# DriveUnit_B-series_ver1_0.net
KiCad netlist of a schematic drawn in EAGLE
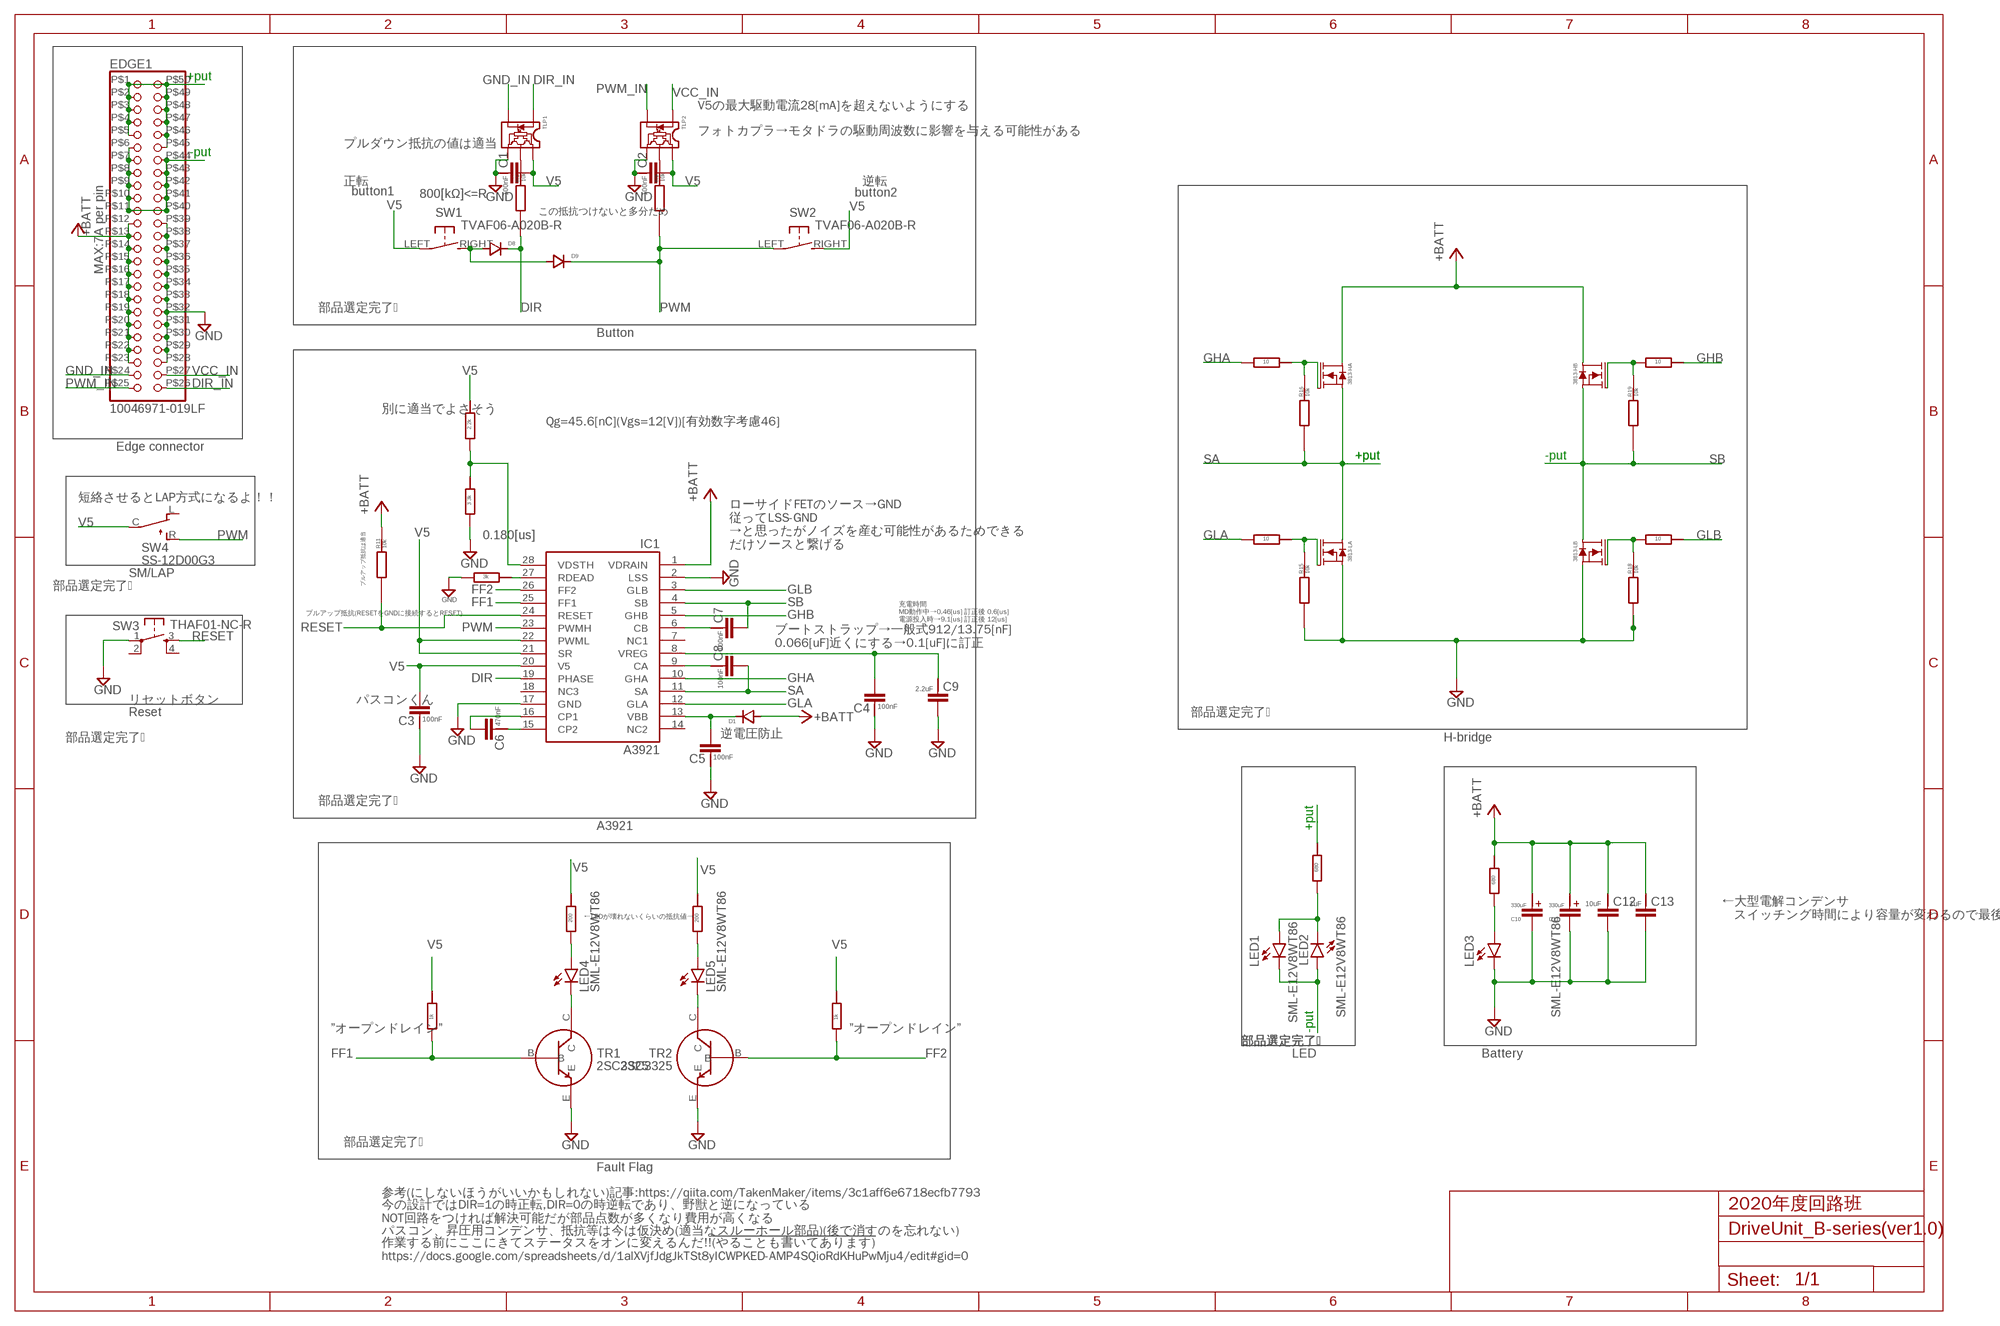
[diagram p0: schematic, sheet 1]

(export (version "E")
  (design (tool "Eeschema 10.0.6"))
  (components
    (comp (ref "3813-HA")
      (value "IRLB3813NOHOLE")
      (footprint "eagle-import:TO-220AB-NOHOLE")
      (libsource (lib "eagle-import") (part "IRLB3813NOHOLE"))
    )
    (comp (ref "3813-HB")
      (value "IRLB3813NOHOLE")
      (footprint "eagle-import:TO-220AB-NOHOLE")
      (libsource (lib "eagle-import") (part "IRLB3813NOHOLE"))
    )
    (comp (ref "3813-LA")
      (value "IRLB3813NOHOLE")
      (footprint "eagle-import:TO-220AB-NOHOLE")
      (libsource (lib "eagle-import") (part "IRLB3813NOHOLE"))
    )
    (comp (ref "3813-LB")
      (value "IRLB3813NOHOLE")
      (footprint "eagle-import:TO-220AB-NOHOLE")
      (libsource (lib "eagle-import") (part "IRLB3813NOHOLE"))
    )
    (comp (ref "C1")
      (value "GCM188L81H104KA57")
      (footprint "eagle-import:GCM188L81H104KA57")
      (libsource (lib "eagle-import") (part "GCM188L81H104KA57"))
    )
    (comp (ref "C2")
      (value "GCM188L81H104KA57")
      (footprint "eagle-import:GCM188L81H104KA57")
      (libsource (lib "eagle-import") (part "GCM188L81H104KA57"))
    )
    (comp (ref "C3")
      (value "GCM188L81H104KA57")
      (footprint "eagle-import:GCM188L81H104KA57")
      (libsource (lib "eagle-import") (part "GCM188L81H104KA57"))
    )
    (comp (ref "C4")
      (value "GCM188L81H104KA57")
      (footprint "eagle-import:GCM188L81H104KA57")
      (libsource (lib "eagle-import") (part "GCM188L81H104KA57"))
    )
    (comp (ref "C5")
      (value "GCM188L81H104KA57")
      (footprint "eagle-import:GCM188L81H104KA57")
      (libsource (lib "eagle-import") (part "GCM188L81H104KA57"))
    )
    (comp (ref "C6")
      (value "GCM21BR71H474KA55")
      (footprint "eagle-import:GCM21BR71H474KA55")
      (libsource (lib "eagle-import") (part "GCM21BR71H474KA55"))
    )
    (comp (ref "C7")
      (value "GCM188L81H104KA57")
      (footprint "eagle-import:GCM188L81H104KA57")
      (libsource (lib "eagle-import") (part "GCM188L81H104KA57"))
    )
    (comp (ref "C8")
      (value "GCM188L81H104KA57")
      (footprint "eagle-import:GCM188L81H104KA57")
      (libsource (lib "eagle-import") (part "GCM188L81H104KA57"))
    )
    (comp (ref "C9")
      (value "GRT31CC81H225KE01L")
      (footprint "eagle-import:GRT31CC81H225KE01L")
      (libsource (lib "eagle-import") (part "GRT31CC81H225KE01L"))
    )
    (comp (ref "C10")
      (value "35PZJ330M10X9")
      (footprint "eagle-import:35PZJ330M10X9")
      (libsource (lib "eagle-import") (part "35PZJ330M10X9"))
    )
    (comp (ref "C11")
      (value "35PZJ330M10X9")
      (footprint "eagle-import:35PZJ330M10X9")
      (libsource (lib "eagle-import") (part "35PZJ330M10X9"))
    )
    (comp (ref "C12")
      (value "GRM32ER7YA106KA12")
      (footprint "eagle-import:GRM32ER7YA106KA12")
      (libsource (lib "eagle-import") (part "GRM32ER7YA106KA12"))
    )
    (comp (ref "C13")
      (value "GRM21BC72A105KE01")
      (footprint "eagle-import:GRM21BC72A105KE01")
      (libsource (lib "eagle-import") (part "GRM21BC72A105KE01"))
    )
    (comp (ref "D1")
      (value "GS1010FL")
      (footprint "eagle-import:GS1010FL")
      (libsource (lib "eagle-import") (part "GS1010FL"))
    )
    (comp (ref "D8")
      (value "GS1010FL")
      (footprint "eagle-import:GS1010FL")
      (libsource (lib "eagle-import") (part "GS1010FL"))
    )
    (comp (ref "D9")
      (value "GS1010FL")
      (footprint "eagle-import:GS1010FL")
      (libsource (lib "eagle-import") (part "GS1010FL"))
    )
    (comp (ref "EDGE1")
      (value "10046971-019LF")
      (footprint "eagle-import:10046971-019LF")
      (libsource (lib "eagle-import") (part "10046971-019LF"))
    )
    (comp (ref "IC1")
      (value "A3921")
      (footprint "eagle-import:A3921")
      (libsource (lib "eagle-import") (part "A3921"))
    )
    (comp (ref "LED1")
      (value "SML-E12V8WT86")
      (footprint "eagle-import:SML-E12V8WT86")
      (libsource (lib "eagle-import") (part "SML-E12V8WT86"))
    )
    (comp (ref "LED2")
      (value "SML-E12V8WT86")
      (footprint "eagle-import:SML-E12V8WT86")
      (libsource (lib "eagle-import") (part "SML-E12V8WT86"))
    )
    (comp (ref "LED3")
      (value "SML-E12V8WT86")
      (footprint "eagle-import:SML-E12V8WT86")
      (libsource (lib "eagle-import") (part "SML-E12V8WT86"))
    )
    (comp (ref "LED4")
      (value "SML-E12V8WT86")
      (footprint "eagle-import:SML-E12V8WT86")
      (libsource (lib "eagle-import") (part "SML-E12V8WT86"))
    )
    (comp (ref "LED5")
      (value "SML-E12V8WT86")
      (footprint "eagle-import:SML-E12V8WT86")
      (libsource (lib "eagle-import") (part "SML-E12V8WT86"))
    )
    (comp (ref "R1")
      (value "RG2012")
      (footprint "eagle-import:RG2012")
      (libsource (lib "eagle-import") (part "RG2012"))
    )
    (comp (ref "R2")
      (value "RG2012N-332-W-T1")
      (footprint "eagle-import:RG2012")
      (libsource (lib "eagle-import") (part "RG2012N-332-W-T1"))
    )
    (comp (ref "R3")
      (value "RG2012P-681-B-T5")
      (footprint "eagle-import:RG2012")
      (libsource (lib "eagle-import") (part "RG2012P-681-B-T5"))
    )
    (comp (ref "R5")
      (value "RG2012-N-102-B-T5")
      (footprint "eagle-import:RG2012")
      (libsource (lib "eagle-import") (part "RG2012-N-102-B-T5"))
    )
    (comp (ref "R6")
      (value "RG2012-N-102-B-T5")
      (footprint "eagle-import:RG2012")
      (libsource (lib "eagle-import") (part "RG2012-N-102-B-T5"))
    )
    (comp (ref "R7")
      (value "RG2012N-201-W-T1")
      (footprint "eagle-import:RG2012")
      (libsource (lib "eagle-import") (part "RG2012N-201-W-T1"))
    )
    (comp (ref "R8")
      (value "RG2012N-201-W-T1")
      (footprint "eagle-import:RG2012")
      (libsource (lib "eagle-import") (part "RG2012N-201-W-T1"))
    )
    (comp (ref "R9")
      (value "RG2012")
      (footprint "eagle-import:RG2012")
      (libsource (lib "eagle-import") (part "RG2012"))
    )
    (comp (ref "R10")
      (value "RG2012Q-100-D-T5")
      (footprint "eagle-import:RG2012")
      (libsource (lib "eagle-import") (part "RG2012Q-100-D-T5"))
    )
    (comp (ref "R11")
      (value "RG2012")
      (footprint "eagle-import:RG2012")
      (libsource (lib "eagle-import") (part "RG2012"))
    )
    (comp (ref "R12")
      (value "RG2012Q-100-D-T5")
      (footprint "eagle-import:RG2012")
      (libsource (lib "eagle-import") (part "RG2012Q-100-D-T5"))
    )
    (comp (ref "R13")
      (value "RG2012P-302-B-T5")
      (footprint "eagle-import:RG2012")
      (libsource (lib "eagle-import") (part "RG2012P-302-B-T5"))
    )
    (comp (ref "R14")
      (value "RG2012N-222-W-T1")
      (footprint "eagle-import:RG2012")
      (libsource (lib "eagle-import") (part "RG2012N-222-W-T1"))
    )
    (comp (ref "R15")
      (value "RG2012")
      (footprint "eagle-import:RG2012")
      (libsource (lib "eagle-import") (part "RG2012"))
    )
    (comp (ref "R16")
      (value "RG2012")
      (footprint "eagle-import:RG2012")
      (libsource (lib "eagle-import") (part "RG2012"))
    )
    (comp (ref "R18")
      (value "RG2012")
      (footprint "eagle-import:RG2012")
      (libsource (lib "eagle-import") (part "RG2012"))
    )
    (comp (ref "R19")
      (value "RG2012")
      (footprint "eagle-import:RG2012")
      (libsource (lib "eagle-import") (part "RG2012"))
    )
    (comp (ref "R20")
      (value "RG2012Q-100-D-T5")
      (footprint "eagle-import:RG2012")
      (libsource (lib "eagle-import") (part "RG2012Q-100-D-T5"))
    )
    (comp (ref "R21")
      (value "RG2012Q-100-D-T5")
      (footprint "eagle-import:RG2012")
      (libsource (lib "eagle-import") (part "RG2012Q-100-D-T5"))
    )
    (comp (ref "R22")
      (value "RG2012P-681-B-T5")
      (footprint "eagle-import:RG2012")
      (libsource (lib "eagle-import") (part "RG2012P-681-B-T5"))
    )
    (comp (ref "SW1")
      (value "TVAF06-A020B-R")
      (footprint "eagle-import:TVAF06-A020B-R")
      (libsource (lib "eagle-import") (part "TVAF06-A020B-R"))
    )
    (comp (ref "SW2")
      (value "TVAF06-A020B-R")
      (footprint "eagle-import:TVAF06-A020B-R")
      (libsource (lib "eagle-import") (part "TVAF06-A020B-R"))
    )
    (comp (ref "SW3")
      (value "THAF01-NC-R")
      (footprint "eagle-import:THAF01-NC-R")
      (libsource (lib "eagle-import") (part "THAF01-NC-R"))
    )
    (comp (ref "SW4")
      (value "SS-12D00G3")
      (footprint "eagle-import:SS-12D00G3")
      (libsource (lib "eagle-import") (part "SS-12D00G3"))
    )
    (comp (ref "TLP1")
      (value "TLP2366")
      (footprint "eagle-import:TLP2366")
      (libsource (lib "eagle-import") (part "TLP2366"))
    )
    (comp (ref "TLP2")
      (value "TLP2366")
      (footprint "eagle-import:TLP2366")
      (libsource (lib "eagle-import") (part "TLP2366"))
    )
    (comp (ref "TR1")
      (value "2SC3325")
      (footprint "eagle-import:2SC3325")
      (libsource (lib "eagle-import") (part "2SC3325"))
    )
    (comp (ref "TR2")
      (value "2SC3325")
      (footprint "eagle-import:2SC3325")
      (libsource (lib "eagle-import") (part "2SC3325"))
    )
  )
  (nets
    (net (code "1") (name "+BATT") (class "Default")
      (node (ref "3813-HA") (pin "DRAIN") (pinfunction "D_DRAIN") (pintype "passive"))
      (node (ref "3813-HB") (pin "DRAIN") (pinfunction "D_DRAIN") (pintype "passive"))
      (node (ref "C10") (pin "A") (pinfunction "ANODE_A") (pintype "bidirectional"))
      (node (ref "C11") (pin "A") (pinfunction "ANODE_A") (pintype "bidirectional"))
      (node (ref "C12") (pin "P$1") (pinfunction "P$1_P$1") (pintype "bidirectional"))
      (node (ref "C13") (pin "P$1") (pinfunction "P$1_P$1") (pintype "bidirectional"))
      (node (ref "D1") (pin "A") (pinfunction "A_A") (pintype "passive"))
      (node (ref "EDGE1") (pin "P$12") (pinfunction "P12_P$12") (pintype "passive"))
      (node (ref "EDGE1") (pin "P$13") (pinfunction "P13_P$13") (pintype "passive"))
      (node (ref "EDGE1") (pin "P$14") (pinfunction "P14_P$14") (pintype "passive"))
      (node (ref "EDGE1") (pin "P$15") (pinfunction "P15_P$15") (pintype "passive"))
      (node (ref "EDGE1") (pin "P$16") (pinfunction "P16_P$16") (pintype "passive"))
      (node (ref "EDGE1") (pin "P$17") (pinfunction "P17_P$17") (pintype "passive"))
      (node (ref "EDGE1") (pin "P$18") (pinfunction "P18_P$18") (pintype "passive"))
      (node (ref "EDGE1") (pin "P$19") (pinfunction "P19_P$19") (pintype "passive"))
      (node (ref "EDGE1") (pin "P$20") (pinfunction "P20_P$20") (pintype "passive"))
      (node (ref "EDGE1") (pin "P$21") (pinfunction "P21_P$21") (pintype "passive"))
      (node (ref "EDGE1") (pin "P$22") (pinfunction "P22_P$22") (pintype "passive"))
      (node (ref "EDGE1") (pin "P$23") (pinfunction "P23_P$23") (pintype "passive"))
      (node (ref "IC1") (pin "1") (pinfunction "VDRAIN_1") (pintype "bidirectional"))
      (node (ref "R11") (pin "RIGHT") (pinfunction "RIGHT_RIGHT") (pintype "bidirectional"))
      (node (ref "R22") (pin "LEFT") (pinfunction "P$1_LEFT") (pintype "bidirectional"))
    )
    (net (code "2") (name "/DIR") (class "Default")
      (node (ref "D8") (pin "C") (pinfunction "C_C") (pintype "passive"))
      (node (ref "IC1") (pin "19") (pinfunction "PHASE_19") (pintype "bidirectional"))
      (node (ref "R1") (pin "LEFT") (pinfunction "LEFT_LEFT") (pintype "bidirectional"))
    )
    (net (code "3") (name "/DIR_IN") (class "Default")
      (node (ref "EDGE1") (pin "P$26") (pinfunction "P26_P$26") (pintype "passive"))
      (node (ref "TLP1") (pin "1") (pinfunction "ANODE_1") (pintype "passive"))
    )
    (net (code "4") (name "/FF1") (class "Default")
      (node (ref "IC1") (pin "25") (pinfunction "FF1_25") (pintype "bidirectional"))
      (node (ref "R5") (pin "RIGHT") (pinfunction "P$2_RIGHT") (pintype "bidirectional"))
      (node (ref "TR1") (pin "B") (pinfunction "B_B") (pintype "bidirectional"))
    )
    (net (code "5") (name "/FF2") (class "Default")
      (node (ref "IC1") (pin "26") (pinfunction "FF2_26") (pintype "bidirectional"))
      (node (ref "R6") (pin "RIGHT") (pinfunction "P$2_RIGHT") (pintype "bidirectional"))
      (node (ref "TR2") (pin "B") (pinfunction "B_B") (pintype "bidirectional"))
    )
    (net (code "6") (name "/GHA") (class "Default")
      (node (ref "IC1") (pin "10") (pinfunction "GHA_10") (pintype "bidirectional"))
      (node (ref "R21") (pin "RIGHT") (pinfunction "P$2_RIGHT") (pintype "bidirectional"))
    )
    (net (code "7") (name "/GHB") (class "Default")
      (node (ref "IC1") (pin "5") (pinfunction "GHB_5") (pintype "bidirectional"))
      (node (ref "R12") (pin "LEFT") (pinfunction "P$1_LEFT") (pintype "bidirectional"))
    )
    (net (code "8") (name "/GLA") (class "Default")
      (node (ref "IC1") (pin "12") (pinfunction "GLA_12") (pintype "bidirectional"))
      (node (ref "R20") (pin "RIGHT") (pinfunction "P$2_RIGHT") (pintype "bidirectional"))
    )
    (net (code "9") (name "/GLB") (class "Default")
      (node (ref "IC1") (pin "3") (pinfunction "GLB_3") (pintype "bidirectional"))
      (node (ref "R10") (pin "LEFT") (pinfunction "P$1_LEFT") (pintype "bidirectional"))
    )
    (net (code "10") (name "/GND_IN") (class "Default")
      (node (ref "EDGE1") (pin "P$24") (pinfunction "P24_P$24") (pintype "passive"))
      (node (ref "TLP1") (pin "3") (pinfunction "CATHODE_3") (pintype "passive"))
    )
    (net (code "11") (name "/PWM") (class "Default")
      (node (ref "D9") (pin "C") (pinfunction "C_C") (pintype "passive"))
      (node (ref "IC1") (pin "23") (pinfunction "PWMH_23") (pintype "bidirectional"))
      (node (ref "R9") (pin "LEFT") (pinfunction "LEFT_LEFT") (pintype "bidirectional"))
      (node (ref "SW2") (pin "LEFT") (pinfunction "P_LEFT") (pintype "passive"))
      (node (ref "SW4") (pin "R") (pinfunction "R_R") (pintype "passive"))
    )
    (net (code "12") (name "/PWM_IN") (class "Default")
      (node (ref "EDGE1") (pin "P$25") (pinfunction "P25_P$25") (pintype "passive"))
      (node (ref "TLP2") (pin "3") (pinfunction "CATHODE_3") (pintype "passive"))
    )
    (net (code "13") (name "/RESET") (class "Default")
      (node (ref "IC1") (pin "24") (pinfunction "RESET_24") (pintype "bidirectional"))
      (node (ref "R11") (pin "LEFT") (pinfunction "LEFT_LEFT") (pintype "bidirectional"))
      (node (ref "SW3") (pin "3") (pinfunction "3_3") (pintype "passive"))
    )
    (net (code "14") (name "/SA") (class "Default")
      (node (ref "3813-HA") (pin "SOURCE") (pinfunction "S_SOURCE") (pintype "passive"))
      (node (ref "3813-LA") (pin "DRAIN") (pinfunction "D_DRAIN") (pintype "passive"))
      (node (ref "C8") (pin "P$2") (pinfunction "P$2_P$2") (pintype "bidirectional"))
      (node (ref "EDGE1") (pin "P$1") (pinfunction "P1_P$1") (pintype "passive"))
      (node (ref "EDGE1") (pin "P$2") (pinfunction "P2_P$2") (pintype "passive"))
      (node (ref "EDGE1") (pin "P$3") (pinfunction "P3_P$3") (pintype "passive"))
      (node (ref "EDGE1") (pin "P$4") (pinfunction "P4_P$4") (pintype "passive"))
      (node (ref "EDGE1") (pin "P$45") (pinfunction "P45_P$45") (pintype "passive"))
      (node (ref "EDGE1") (pin "P$46") (pinfunction "P46_P$46") (pintype "passive"))
      (node (ref "EDGE1") (pin "P$47") (pinfunction "P47_P$47") (pintype "passive"))
      (node (ref "EDGE1") (pin "P$48") (pinfunction "P48_P$48") (pintype "passive"))
      (node (ref "EDGE1") (pin "P$49") (pinfunction "P49_P$49") (pintype "passive"))
      (node (ref "EDGE1") (pin "P$5") (pinfunction "P5_P$5") (pintype "passive"))
      (node (ref "EDGE1") (pin "P$50") (pinfunction "P50_P$50") (pintype "passive"))
      (node (ref "IC1") (pin "11") (pinfunction "SA_11") (pintype "bidirectional"))
      (node (ref "R16") (pin "LEFT") (pinfunction "LEFT_LEFT") (pintype "bidirectional"))
      (node (ref "R3") (pin "LEFT") (pinfunction "P$1_LEFT") (pintype "bidirectional"))
    )
    (net (code "15") (name "/SB") (class "Default")
      (node (ref "3813-HB") (pin "SOURCE") (pinfunction "S_SOURCE") (pintype "passive"))
      (node (ref "3813-LB") (pin "DRAIN") (pinfunction "D_DRAIN") (pintype "passive"))
      (node (ref "C7") (pin "P$2") (pinfunction "P$2_P$2") (pintype "bidirectional"))
      (node (ref "EDGE1") (pin "P$10") (pinfunction "P10_P$10") (pintype "passive"))
      (node (ref "EDGE1") (pin "P$11") (pinfunction "P11_P$11") (pintype "passive"))
      (node (ref "EDGE1") (pin "P$40") (pinfunction "P40_P$40") (pintype "passive"))
      (node (ref "EDGE1") (pin "P$41") (pinfunction "P41_P$41") (pintype "passive"))
      (node (ref "EDGE1") (pin "P$42") (pinfunction "P42_P$42") (pintype "passive"))
      (node (ref "EDGE1") (pin "P$43") (pinfunction "P43_P$43") (pintype "passive"))
      (node (ref "EDGE1") (pin "P$44") (pinfunction "P44_P$44") (pintype "passive"))
      (node (ref "EDGE1") (pin "P$6") (pinfunction "P6_P$6") (pintype "passive"))
      (node (ref "EDGE1") (pin "P$7") (pinfunction "P7_P$7") (pintype "passive"))
      (node (ref "EDGE1") (pin "P$8") (pinfunction "P8_P$8") (pintype "passive"))
      (node (ref "EDGE1") (pin "P$9") (pinfunction "P9_P$9") (pintype "passive"))
      (node (ref "IC1") (pin "4") (pinfunction "SB_4") (pintype "bidirectional"))
      (node (ref "LED1") (pin "K") (pinfunction "C_K") (pintype "passive"))
      (node (ref "LED2") (pin "A") (pinfunction "A_A") (pintype "passive"))
      (node (ref "R19") (pin "LEFT") (pinfunction "LEFT_LEFT") (pintype "bidirectional"))
    )
    (net (code "16") (name "/V5") (class "Default")
      (node (ref "C1") (pin "P$2") (pinfunction "P$2_P$2") (pintype "bidirectional"))
      (node (ref "C2") (pin "P$2") (pinfunction "P$2_P$2") (pintype "bidirectional"))
      (node (ref "C3") (pin "P$2") (pinfunction "P$2_P$2") (pintype "bidirectional"))
      (node (ref "IC1") (pin "20") (pinfunction "V5_20") (pintype "bidirectional"))
      (node (ref "IC1") (pin "21") (pinfunction "SR_21") (pintype "bidirectional"))
      (node (ref "IC1") (pin "22") (pinfunction "PWML_22") (pintype "bidirectional"))
      (node (ref "R14") (pin "LEFT") (pinfunction "P$1_LEFT") (pintype "bidirectional"))
      (node (ref "R5") (pin "LEFT") (pinfunction "P$1_LEFT") (pintype "bidirectional"))
      (node (ref "R6") (pin "LEFT") (pinfunction "P$1_LEFT") (pintype "bidirectional"))
      (node (ref "R7") (pin "LEFT") (pinfunction "P$1_LEFT") (pintype "bidirectional"))
      (node (ref "R8") (pin "LEFT") (pinfunction "P$1_LEFT") (pintype "bidirectional"))
      (node (ref "SW1") (pin "LEFT") (pinfunction "P_LEFT") (pintype "passive"))
      (node (ref "SW2") (pin "RIGHT") (pinfunction "S_RIGHT") (pintype "passive"))
      (node (ref "SW4") (pin "C") (pinfunction "C_C") (pintype "passive"))
      (node (ref "TLP1") (pin "6") (pinfunction "VCC_6") (pintype "passive"))
      (node (ref "TLP2") (pin "6") (pinfunction "VCC_6") (pintype "passive"))
    )
    (net (code "17") (name "/VCC_IN") (class "Default")
      (node (ref "EDGE1") (pin "P$27") (pinfunction "P27_P$27") (pintype "passive"))
      (node (ref "TLP2") (pin "1") (pinfunction "ANODE_1") (pintype "passive"))
    )
    (net (code "18") (name "GND") (class "Default")
      (node (ref "3813-LA") (pin "SOURCE") (pinfunction "S_SOURCE") (pintype "passive"))
      (node (ref "3813-LB") (pin "SOURCE") (pinfunction "S_SOURCE") (pintype "passive"))
      (node (ref "C1") (pin "P$1") (pinfunction "P$1_P$1") (pintype "bidirectional"))
      (node (ref "C10") (pin "C") (pinfunction "CATHODE_C") (pintype "bidirectional"))
      (node (ref "C11") (pin "C") (pinfunction "CATHODE_C") (pintype "bidirectional"))
      (node (ref "C12") (pin "P$2") (pinfunction "P$2_P$2") (pintype "bidirectional"))
      (node (ref "C13") (pin "P$2") (pinfunction "P$2_P$2") (pintype "bidirectional"))
      (node (ref "C2") (pin "P$1") (pinfunction "P$1_P$1") (pintype "bidirectional"))
      (node (ref "C3") (pin "P$1") (pinfunction "P$1_P$1") (pintype "bidirectional"))
      (node (ref "C4") (pin "P$1") (pinfunction "P$1_P$1") (pintype "bidirectional"))
      (node (ref "C5") (pin "P$1") (pinfunction "P$1_P$1") (pintype "bidirectional"))
      (node (ref "C9") (pin "P$2") (pinfunction "P$2_P$2") (pintype "bidirectional"))
      (node (ref "EDGE1") (pin "P$28") (pinfunction "P28_P$28") (pintype "passive"))
      (node (ref "EDGE1") (pin "P$29") (pinfunction "P29_P$29") (pintype "passive"))
      (node (ref "EDGE1") (pin "P$30") (pinfunction "P30_P$30") (pintype "passive"))
      (node (ref "EDGE1") (pin "P$31") (pinfunction "P31_P$31") (pintype "passive"))
      (node (ref "EDGE1") (pin "P$32") (pinfunction "P32_P$32") (pintype "passive"))
      (node (ref "EDGE1") (pin "P$33") (pinfunction "P33_P$33") (pintype "passive"))
      (node (ref "EDGE1") (pin "P$34") (pinfunction "P34_P$34") (pintype "passive"))
      (node (ref "EDGE1") (pin "P$35") (pinfunction "P35_P$35") (pintype "passive"))
      (node (ref "EDGE1") (pin "P$36") (pinfunction "P36_P$36") (pintype "passive"))
      (node (ref "EDGE1") (pin "P$37") (pinfunction "P37_P$37") (pintype "passive"))
      (node (ref "EDGE1") (pin "P$38") (pinfunction "P38_P$38") (pintype "passive"))
      (node (ref "EDGE1") (pin "P$39") (pinfunction "P39_P$39") (pintype "passive"))
      (node (ref "IC1") (pin "17") (pinfunction "GND_17") (pintype "bidirectional"))
      (node (ref "IC1") (pin "2") (pinfunction "LSS_2") (pintype "bidirectional"))
      (node (ref "LED3") (pin "K") (pinfunction "C_K") (pintype "passive"))
      (node (ref "R13") (pin "RIGHT") (pinfunction "P$2_RIGHT") (pintype "bidirectional"))
      (node (ref "R15") (pin "LEFT") (pinfunction "LEFT_LEFT") (pintype "bidirectional"))
      (node (ref "R18") (pin "LEFT") (pinfunction "LEFT_LEFT") (pintype "bidirectional"))
      (node (ref "R2") (pin "RIGHT") (pinfunction "P$2_RIGHT") (pintype "bidirectional"))
      (node (ref "SW3") (pin "1") (pinfunction "1_1") (pintype "passive"))
      (node (ref "TLP1") (pin "4") (pinfunction "GND_4") (pintype "passive"))
      (node (ref "TLP2") (pin "4") (pinfunction "GND_4") (pintype "passive"))
      (node (ref "TR1") (pin "E") (pinfunction "E_E") (pintype "bidirectional"))
      (node (ref "TR2") (pin "E") (pinfunction "E_E") (pintype "bidirectional"))
    )
    (net (code "19") (name "Net-(3813-HA-G)") (class "Default")
      (node (ref "3813-HA") (pin "GATE") (pinfunction "G_GATE") (pintype "passive"))
      (node (ref "R16") (pin "RIGHT") (pinfunction "RIGHT_RIGHT") (pintype "bidirectional"))
      (node (ref "R21") (pin "LEFT") (pinfunction "P$1_LEFT") (pintype "bidirectional"))
    )
    (net (code "20") (name "Net-(3813-HB-G)") (class "Default")
      (node (ref "3813-HB") (pin "GATE") (pinfunction "G_GATE") (pintype "passive"))
      (node (ref "R12") (pin "RIGHT") (pinfunction "P$2_RIGHT") (pintype "bidirectional"))
      (node (ref "R19") (pin "RIGHT") (pinfunction "RIGHT_RIGHT") (pintype "bidirectional"))
    )
    (net (code "21") (name "Net-(3813-LA-G)") (class "Default")
      (node (ref "3813-LA") (pin "GATE") (pinfunction "G_GATE") (pintype "passive"))
      (node (ref "R15") (pin "RIGHT") (pinfunction "RIGHT_RIGHT") (pintype "bidirectional"))
      (node (ref "R20") (pin "LEFT") (pinfunction "P$1_LEFT") (pintype "bidirectional"))
    )
    (net (code "22") (name "Net-(3813-LB-G)") (class "Default")
      (node (ref "3813-LB") (pin "GATE") (pinfunction "G_GATE") (pintype "passive"))
      (node (ref "R10") (pin "RIGHT") (pinfunction "P$2_RIGHT") (pintype "bidirectional"))
      (node (ref "R18") (pin "RIGHT") (pinfunction "RIGHT_RIGHT") (pintype "bidirectional"))
    )
    (net (code "23") (name "Net-(IC1-CA)") (class "Default")
      (node (ref "C8") (pin "P$1") (pinfunction "P$1_P$1") (pintype "bidirectional"))
      (node (ref "IC1") (pin "9") (pinfunction "CA_9") (pintype "bidirectional"))
    )
    (net (code "24") (name "Net-(IC1-CB)") (class "Default")
      (node (ref "C7") (pin "P$1") (pinfunction "P$1_P$1") (pintype "bidirectional"))
      (node (ref "IC1") (pin "6") (pinfunction "CB_6") (pintype "bidirectional"))
    )
    (net (code "25") (name "Net-(IC1-CP1)") (class "Default")
      (node (ref "C6") (pin "P$2") (pinfunction "P$2_P$2") (pintype "bidirectional"))
      (node (ref "IC1") (pin "16") (pinfunction "CP1_16") (pintype "bidirectional"))
    )
    (net (code "26") (name "Net-(IC1-CP2)") (class "Default")
      (node (ref "C6") (pin "P$1") (pinfunction "P$1_P$1") (pintype "bidirectional"))
      (node (ref "IC1") (pin "15") (pinfunction "CP2_15") (pintype "bidirectional"))
    )
    (net (code "27") (name "Net-(IC1-RDEAD)") (class "Default")
      (node (ref "IC1") (pin "27") (pinfunction "RDEAD_27") (pintype "bidirectional"))
      (node (ref "R13") (pin "LEFT") (pinfunction "P$1_LEFT") (pintype "bidirectional"))
    )
    (net (code "28") (name "Net-(IC1-VBB)") (class "Default")
      (node (ref "C5") (pin "P$2") (pinfunction "P$2_P$2") (pintype "bidirectional"))
      (node (ref "D1") (pin "C") (pinfunction "C_C") (pintype "passive"))
      (node (ref "IC1") (pin "13") (pinfunction "VBB_13") (pintype "bidirectional"))
    )
    (net (code "29") (name "Net-(IC1-VDSTH)") (class "Default")
      (node (ref "IC1") (pin "28") (pinfunction "VDSTH_28") (pintype "bidirectional"))
      (node (ref "R14") (pin "RIGHT") (pinfunction "P$2_RIGHT") (pintype "bidirectional"))
      (node (ref "R2") (pin "LEFT") (pinfunction "P$1_LEFT") (pintype "bidirectional"))
    )
    (net (code "30") (name "Net-(IC1-VREG)") (class "Default")
      (node (ref "C4") (pin "P$2") (pinfunction "P$2_P$2") (pintype "bidirectional"))
      (node (ref "C9") (pin "P$1") (pinfunction "P$1_P$1") (pintype "bidirectional"))
      (node (ref "IC1") (pin "8") (pinfunction "VREG_8") (pintype "bidirectional"))
    )
    (net (code "31") (name "Net-(LED2-C)") (class "Default")
      (node (ref "LED1") (pin "A") (pinfunction "A_A") (pintype "passive"))
      (node (ref "LED2") (pin "K") (pinfunction "C_K") (pintype "passive"))
      (node (ref "R3") (pin "RIGHT") (pinfunction "P$2_RIGHT") (pintype "bidirectional"))
    )
    (net (code "32") (name "Net-(LED4-C)") (class "Default")
      (node (ref "LED4") (pin "K") (pinfunction "C_K") (pintype "passive"))
      (node (ref "TR1") (pin "C") (pinfunction "C_C") (pintype "bidirectional"))
    )
    (net (code "33") (name "Net-(LED5-C)") (class "Default")
      (node (ref "LED5") (pin "K") (pinfunction "C_K") (pintype "passive"))
      (node (ref "TR2") (pin "C") (pinfunction "C_C") (pintype "bidirectional"))
    )
    (net (code "34") (name "Net-(R7-P$2)") (class "Default")
      (node (ref "LED4") (pin "A") (pinfunction "A_A") (pintype "passive"))
      (node (ref "R7") (pin "RIGHT") (pinfunction "P$2_RIGHT") (pintype "bidirectional"))
    )
    (net (code "35") (name "Net-(R8-P$2)") (class "Default")
      (node (ref "LED5") (pin "A") (pinfunction "A_A") (pintype "passive"))
      (node (ref "R8") (pin "RIGHT") (pinfunction "P$2_RIGHT") (pintype "bidirectional"))
    )
    (net (code "36") (name "Net-(R22-P$2)") (class "Default")
      (node (ref "LED3") (pin "A") (pinfunction "A_A") (pintype "passive"))
      (node (ref "R22") (pin "RIGHT") (pinfunction "P$2_RIGHT") (pintype "bidirectional"))
    )
    (net (code "37") (name "Net-(SW1-S)") (class "Default")
      (node (ref "D8") (pin "A") (pinfunction "A_A") (pintype "passive"))
      (node (ref "D9") (pin "A") (pinfunction "A_A") (pintype "passive"))
      (node (ref "SW1") (pin "RIGHT") (pinfunction "S_RIGHT") (pintype "passive"))
    )
    (net (code "38") (name "Net-(TLP1-VOUT)") (class "Default")
      (node (ref "R1") (pin "RIGHT") (pinfunction "RIGHT_RIGHT") (pintype "bidirectional"))
      (node (ref "TLP1") (pin "5") (pinfunction "VOUT_5") (pintype "passive"))
    )
    (net (code "39") (name "Net-(TLP2-VOUT)") (class "Default")
      (node (ref "R9") (pin "RIGHT") (pinfunction "RIGHT_RIGHT") (pintype "bidirectional"))
      (node (ref "TLP2") (pin "5") (pinfunction "VOUT_5") (pintype "passive"))
    )
    (net (code "40") (name "unconnected-(IC1-NC1-Pad7)") (class "Default")
      (node (ref "IC1") (pin "7") (pinfunction "NC1_7") (pintype "bidirectional"))
    )
    (net (code "41") (name "unconnected-(IC1-NC2-Pad14)") (class "Default")
      (node (ref "IC1") (pin "14") (pinfunction "NC2_14") (pintype "bidirectional"))
    )
    (net (code "42") (name "unconnected-(IC1-NC3-Pad18)") (class "Default")
      (node (ref "IC1") (pin "18") (pinfunction "NC3_18") (pintype "bidirectional"))
    )
    (net (code "43") (name "unconnected-(SW3-Pad2)") (class "Default")
      (node (ref "SW3") (pin "2") (pinfunction "2_2") (pintype "passive"))
    )
    (net (code "44") (name "unconnected-(SW3-Pad4)") (class "Default")
      (node (ref "SW3") (pin "4") (pinfunction "4_4") (pintype "passive"))
    )
    (net (code "45") (name "unconnected-(SW4-PadL)") (class "Default")
      (node (ref "SW4") (pin "L") (pinfunction "L_L") (pintype "passive"))
    )
  )
)
